# harp_RBG_array_v1_0.net
KiCad netlist of a schematic drawn in EAGLE
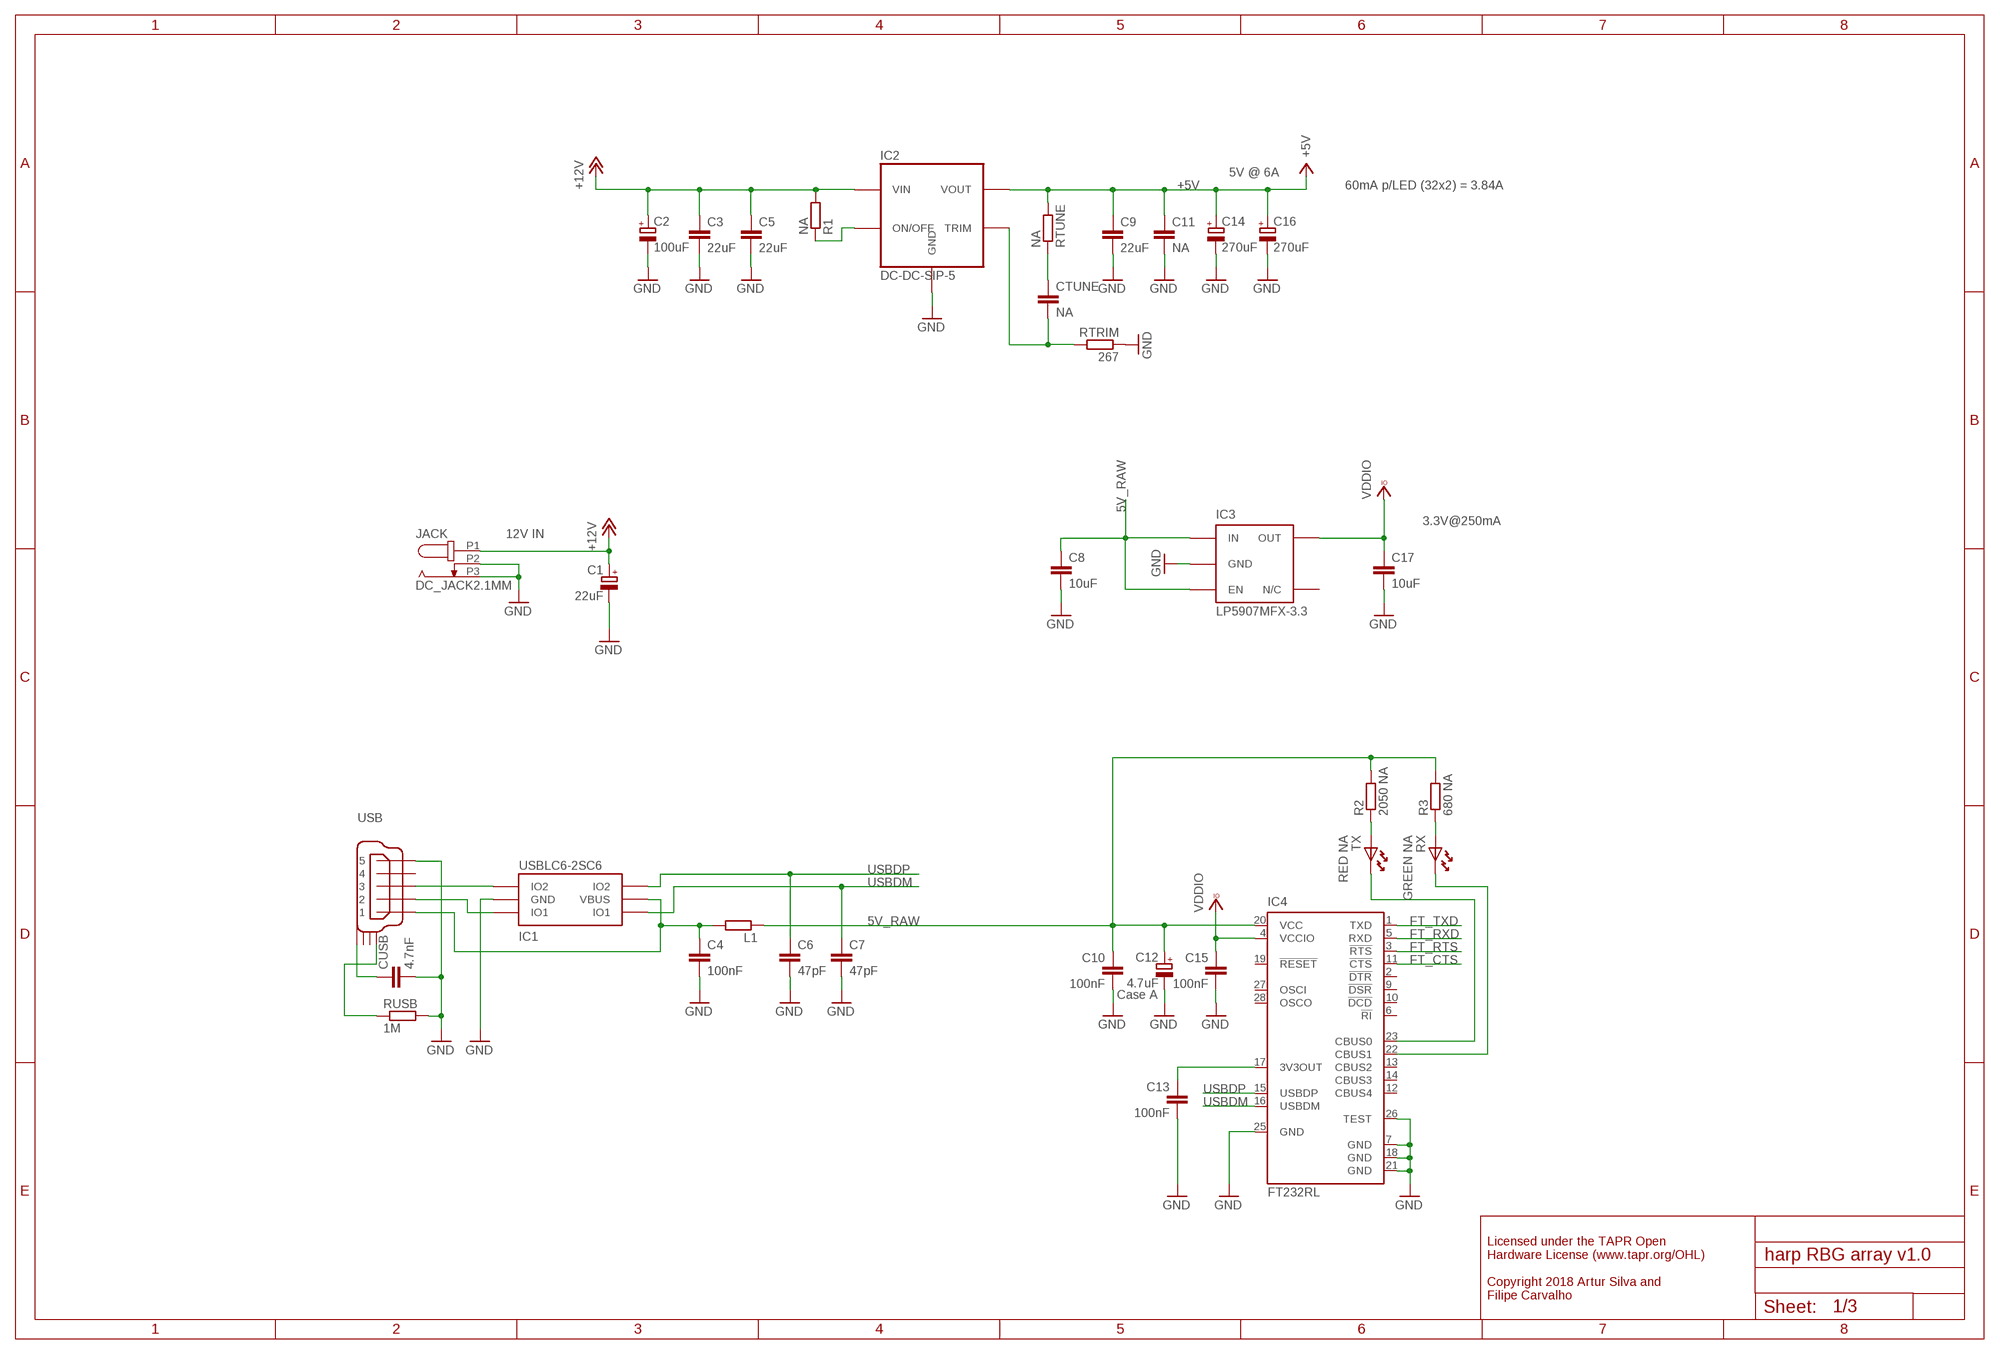
[diagram p0: schematic, sheet 1]
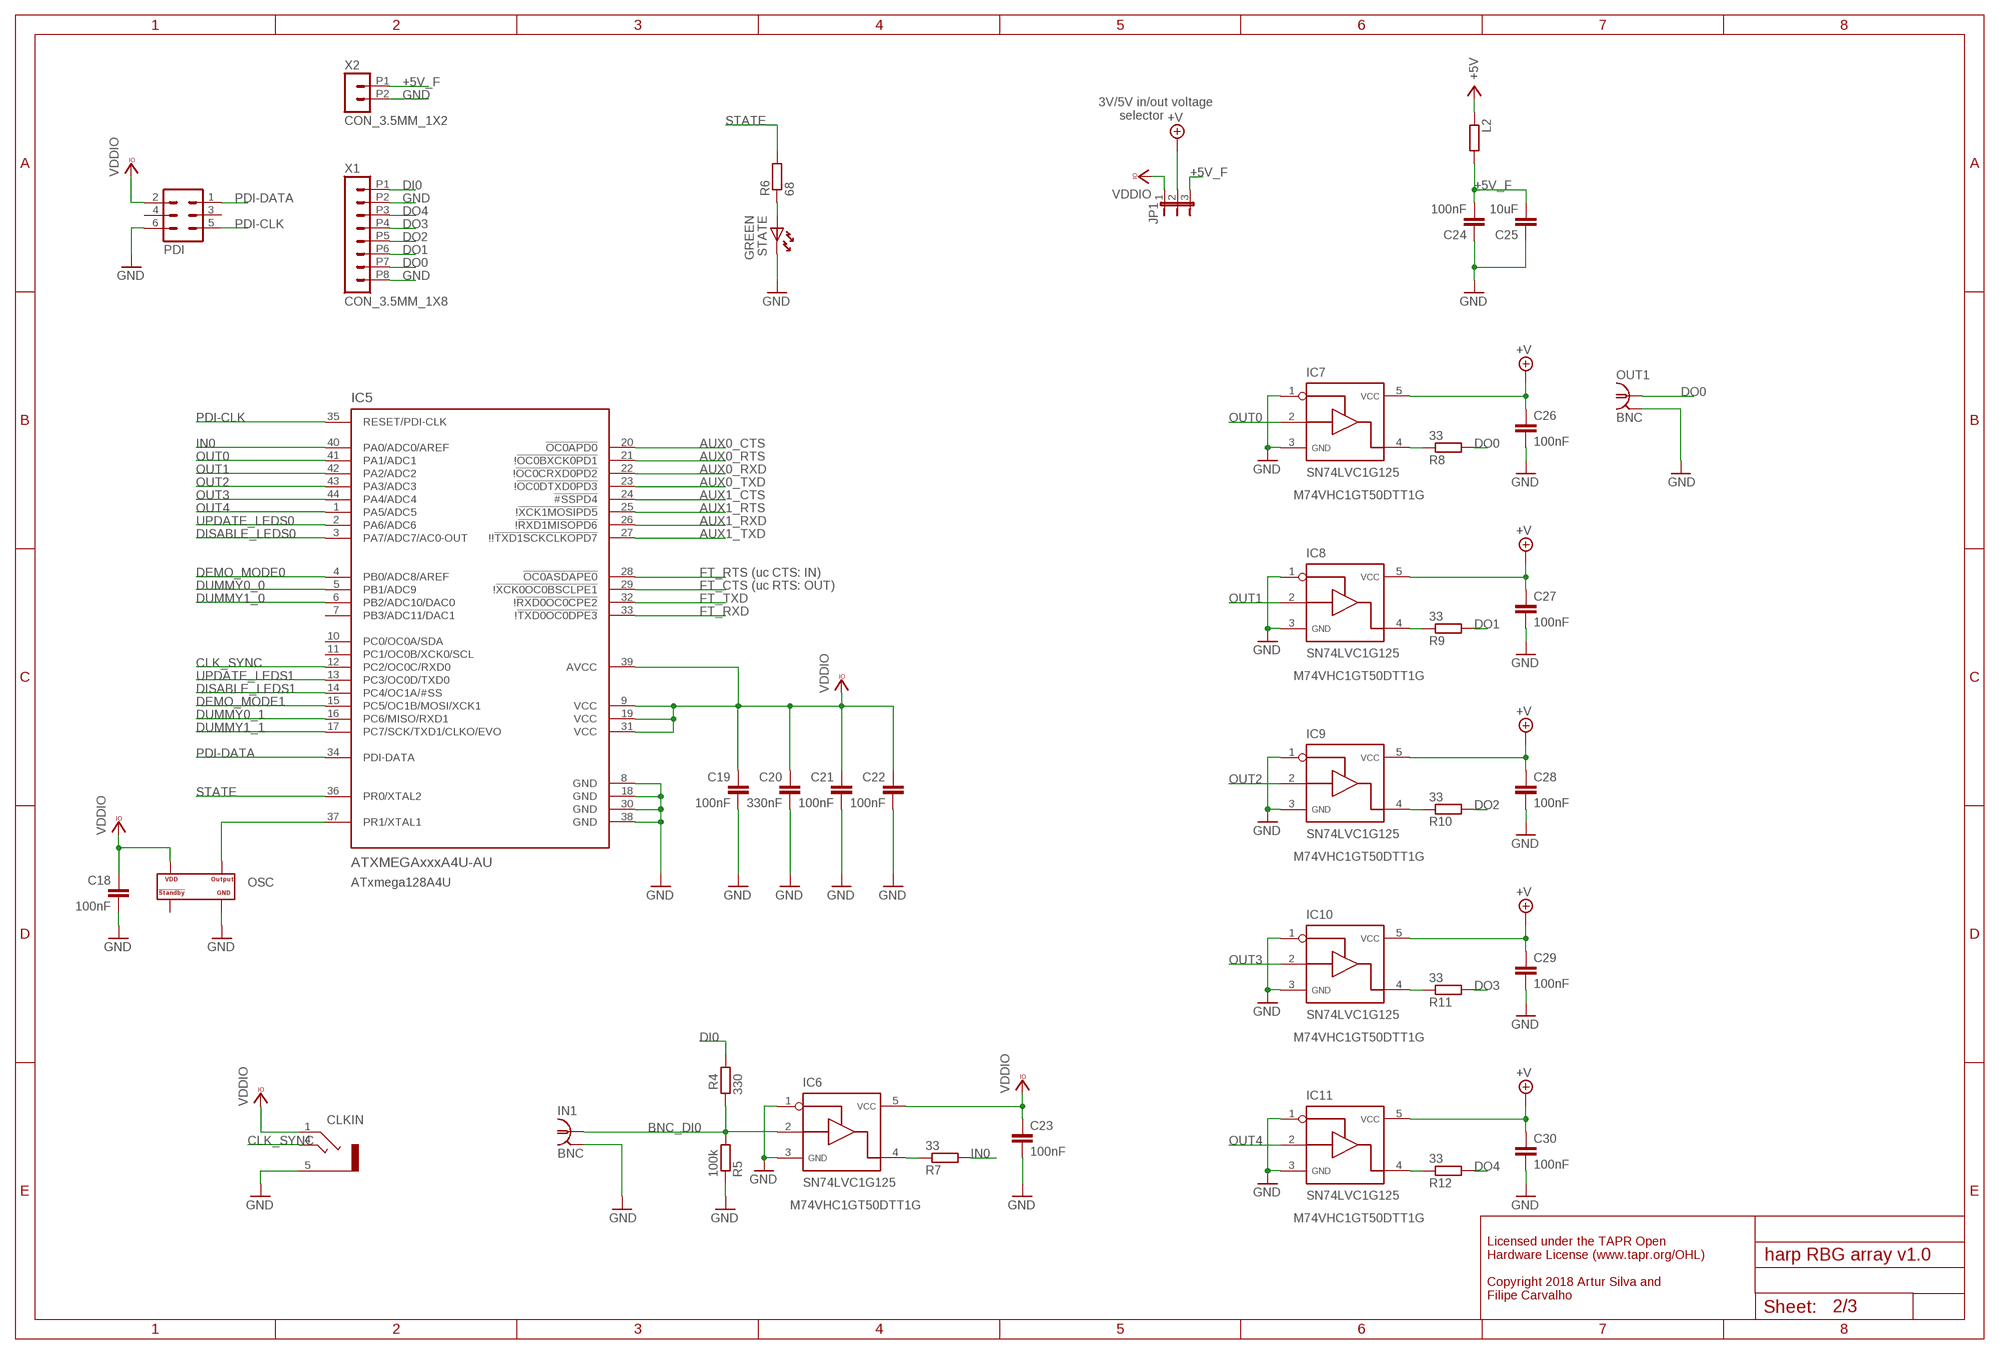
[diagram p1: schematic, sheet 2]
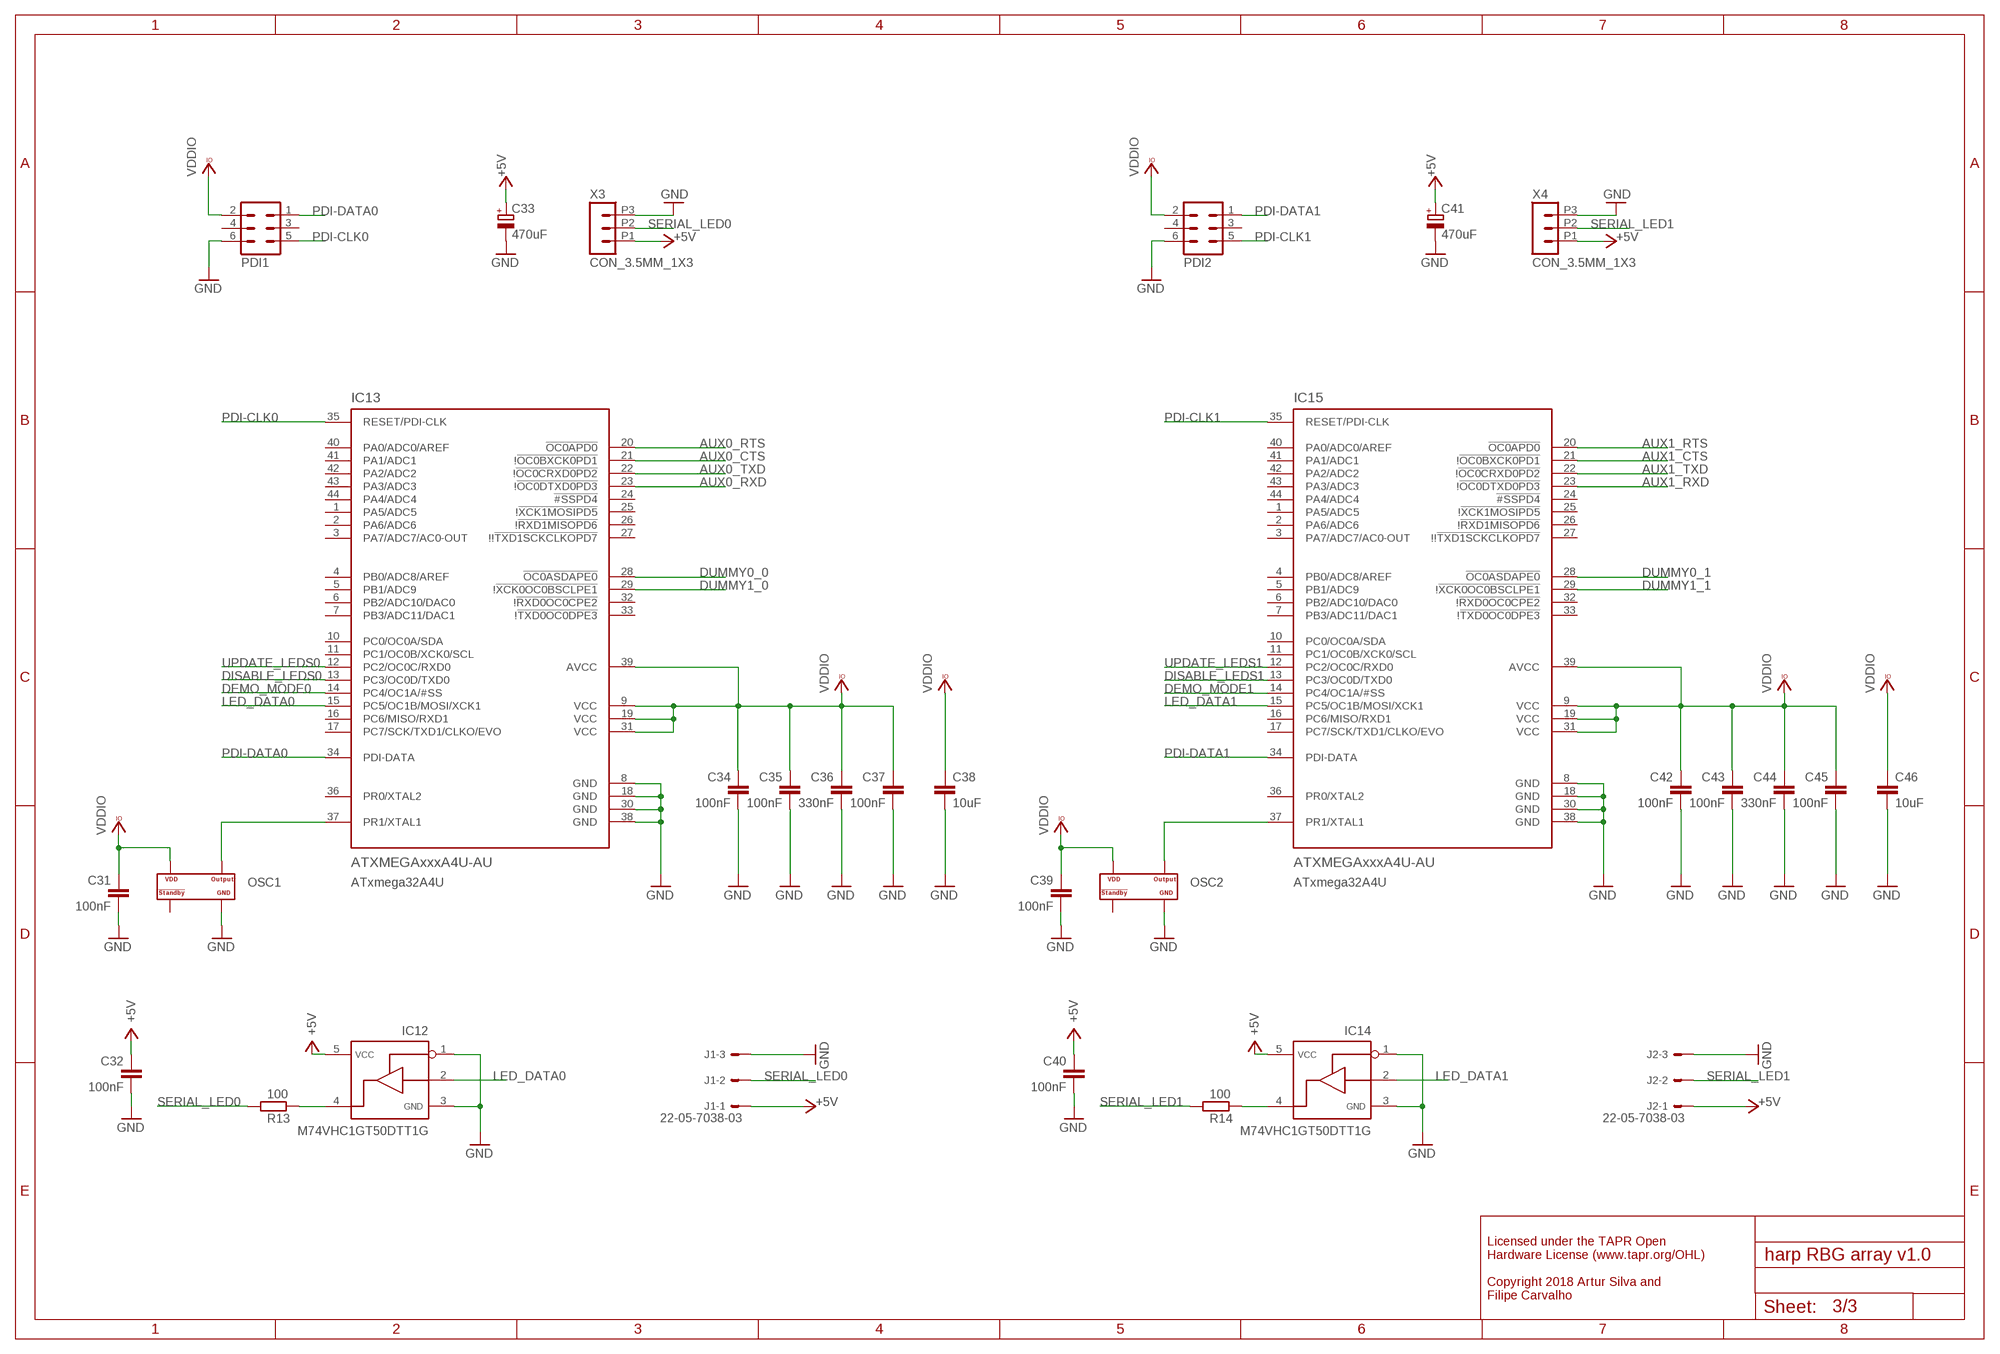
[diagram p2: schematic, sheet 3]

(export (version "E")
  (design (tool "Eeschema 10.0.6"))
  (components
    (comp (ref "C1")
      (value "22uF")
      (footprint "eagle-import:CAP_100UF_HAND")
      (libsource (lib "eagle-import") (part "CAP_100UFHAND"))
    )
    (comp (ref "C2")
      (value "100uF")
      (footprint "eagle-import:PANASONIC_E")
      (libsource (lib "eagle-import") (part "CPOL-EUE"))
    )
    (comp (ref "C3")
      (value "22uF")
      (footprint "eagle-import:C1210")
      (libsource (lib "eagle-import") (part "C-EUC1210"))
    )
    (comp (ref "C4")
      (value "100nF")
      (footprint "eagle-import:C0402")
      (libsource (lib "eagle-import") (part "C-EUC0402"))
    )
    (comp (ref "C5")
      (value "22uF")
      (footprint "eagle-import:C1210")
      (libsource (lib "eagle-import") (part "C-EUC1210"))
    )
    (comp (ref "C6")
      (value "47pF")
      (footprint "eagle-import:C0402")
      (libsource (lib "eagle-import") (part "C-EUC0402"))
    )
    (comp (ref "C7")
      (value "47pF")
      (footprint "eagle-import:C0402")
      (libsource (lib "eagle-import") (part "C-EUC0402"))
    )
    (comp (ref "C8")
      (value "10uF")
      (footprint "eagle-import:C0603")
      (libsource (lib "eagle-import") (part "C-EUC0603"))
    )
    (comp (ref "C9")
      (value "22uF")
      (footprint "eagle-import:C1210")
      (libsource (lib "eagle-import") (part "C-EUC1210"))
    )
    (comp (ref "C10")
      (value "100nF")
      (footprint "eagle-import:C0402")
      (libsource (lib "eagle-import") (part "C-EUC0402"))
    )
    (comp (ref "C11")
      (value "NA")
      (footprint "eagle-import:C1210")
      (libsource (lib "eagle-import") (part "C-EUC1210"))
    )
    (comp (ref "C12")
      (value "4.7uF")
      (footprint "eagle-import:A_3216-18W")
      (libsource (lib "eagle-import") (part "CPOL-EUA/3216-18W"))
    )
    (comp (ref "C13")
      (value "100nF")
      (footprint "eagle-import:C0402")
      (libsource (lib "eagle-import") (part "C-EUC0402"))
    )
    (comp (ref "C14")
      (value "270uF")
      (footprint "eagle-import:PANASONIC_E")
      (libsource (lib "eagle-import") (part "CPOL-EUE"))
    )
    (comp (ref "C15")
      (value "100nF")
      (footprint "eagle-import:C0402")
      (libsource (lib "eagle-import") (part "C-EUC0402"))
    )
    (comp (ref "C16")
      (value "270uF")
      (footprint "eagle-import:PANASONIC_E")
      (libsource (lib "eagle-import") (part "CPOL-EUE"))
    )
    (comp (ref "C17")
      (value "10uF")
      (footprint "eagle-import:C0603")
      (libsource (lib "eagle-import") (part "C-EUC0603"))
    )
    (comp (ref "CTUNE")
      (value "NA")
      (footprint "eagle-import:C0402")
      (libsource (lib "eagle-import") (part "C-EUC0402"))
    )
    (comp (ref "CUSB")
      (value "4.7nF")
      (footprint "eagle-import:C0402")
      (libsource (lib "eagle-import") (part "C-EUC0402"))
    )
    (comp (ref "IC1")
      (value "USBLC6-2SC6")
      (footprint "eagle-import:SOT23-6L")
      (libsource (lib "eagle-import") (part "USBLC6-2"))
    )
    (comp (ref "IC2")
      (value "DC-DC-SIP-5")
      (footprint "eagle-import:SIP-5")
      (libsource (lib "eagle-import") (part "DC-DC-SIP-5"))
    )
    (comp (ref "IC3")
      (value "LP5907MFX-3.3")
      (footprint "eagle-import:TSOT23-5")
      (libsource (lib "eagle-import") (part "TLV700XX"))
    )
    (comp (ref "IC4")
      (value "FT232RL")
      (footprint "eagle-import:SSOP28")
      (libsource (lib "eagle-import") (part "FT232RL"))
    )
    (comp (ref "JACK")
      (value "DC_JACK2.1MM")
      (footprint "eagle-import:DC_POWER_INPUT_2.1MM")
      (libsource (lib "eagle-import") (part "DC_JACK2.1MM"))
    )
    (comp (ref "L1")
      (value "???")
      (footprint "eagle-import:R0805")
      (libsource (lib "eagle-import") (part "R-EU_R0805"))
    )
    (comp (ref "R1")
      (value "NA")
      (footprint "eagle-import:R0402")
      (libsource (lib "eagle-import") (part "R-EU_R0402"))
    )
    (comp (ref "R2")
      (value "2050 NA")
      (footprint "eagle-import:R0402")
      (libsource (lib "eagle-import") (part "R-EU_R0402"))
    )
    (comp (ref "R3")
      (value "680 NA")
      (footprint "eagle-import:R0402")
      (libsource (lib "eagle-import") (part "R-EU_R0402"))
    )
    (comp (ref "RTRIM")
      (value "267")
      (footprint "eagle-import:R0402")
      (libsource (lib "eagle-import") (part "R-EU_R0402"))
    )
    (comp (ref "RTUNE")
      (value "NA")
      (footprint "eagle-import:R0402")
      (libsource (lib "eagle-import") (part "R-EU_R0402"))
    )
    (comp (ref "RUSB")
      (value "1M")
      (footprint "eagle-import:R0402")
      (libsource (lib "eagle-import") (part "R-EU_R0402"))
    )
    (comp (ref "RX")
      (value "GREEN NA")
      (footprint "eagle-import:LED_HAND")
      (libsource (lib "eagle-import") (part "LEDHAND"))
    )
    (comp (ref "TX")
      (value "RED NA")
      (footprint "eagle-import:LED_HAND")
      (libsource (lib "eagle-import") (part "LEDHAND"))
    )
    (comp (ref "USB")
      (value "USB_MINI_B")
      (footprint "eagle-import:240-0002-1")
      (libsource (lib "eagle-import") (part "USB_MINI_B"))
    )
    (comp (ref "C31")
      (value "100nF")
      (footprint "eagle-import:C0402")
      (libsource (lib "eagle-import") (part "C-EUC0402"))
    )
    (comp (ref "C32")
      (value "100nF")
      (footprint "eagle-import:C0402")
      (libsource (lib "eagle-import") (part "C-EUC0402"))
    )
    (comp (ref "C33")
      (value "470uF")
      (footprint "eagle-import:E3,5-8")
      (libsource (lib "eagle-import") (part "resistor_CPOL-EUE3.5-8"))
    )
    (comp (ref "C34")
      (value "100nF")
      (footprint "eagle-import:C0402")
      (libsource (lib "eagle-import") (part "C-EUC0402"))
    )
    (comp (ref "C35")
      (value "100nF")
      (footprint "eagle-import:C0402")
      (libsource (lib "eagle-import") (part "C-EUC0402"))
    )
    (comp (ref "C36")
      (value "330nF")
      (footprint "eagle-import:C0402")
      (libsource (lib "eagle-import") (part "C-EUC0402"))
    )
    (comp (ref "C37")
      (value "100nF")
      (footprint "eagle-import:C0402")
      (libsource (lib "eagle-import") (part "C-EUC0402"))
    )
    (comp (ref "C38")
      (value "10uF")
      (footprint "eagle-import:C0603")
      (libsource (lib "eagle-import") (part "C-EUC0603"))
    )
    (comp (ref "C39")
      (value "100nF")
      (footprint "eagle-import:C0402")
      (libsource (lib "eagle-import") (part "C-EUC0402"))
    )
    (comp (ref "C40")
      (value "100nF")
      (footprint "eagle-import:C0402")
      (libsource (lib "eagle-import") (part "C-EUC0402"))
    )
    (comp (ref "C41")
      (value "470uF")
      (footprint "eagle-import:E3,5-8")
      (libsource (lib "eagle-import") (part "resistor_CPOL-EUE3.5-8"))
    )
    (comp (ref "C42")
      (value "100nF")
      (footprint "eagle-import:C0402")
      (libsource (lib "eagle-import") (part "C-EUC0402"))
    )
    (comp (ref "C43")
      (value "100nF")
      (footprint "eagle-import:C0402")
      (libsource (lib "eagle-import") (part "C-EUC0402"))
    )
    (comp (ref "C44")
      (value "330nF")
      (footprint "eagle-import:C0402")
      (libsource (lib "eagle-import") (part "C-EUC0402"))
    )
    (comp (ref "C45")
      (value "100nF")
      (footprint "eagle-import:C0402")
      (libsource (lib "eagle-import") (part "C-EUC0402"))
    )
    (comp (ref "C46")
      (value "10uF")
      (footprint "eagle-import:C0603")
      (libsource (lib "eagle-import") (part "C-EUC0603"))
    )
    (comp (ref "IC12")
      (value "M74VHC1GT50DTT1G")
      (footprint "eagle-import:SOT23-5")
      (libsource (lib "eagle-import") (part "SN74LVC1G125"))
    )
    (comp (ref "IC13")
      (value "ATXMEGAxxxA4U-AU")
      (footprint "eagle-import:QFP80P1200X1200X120-44N")
      (libsource (lib "eagle-import") (part "AT-XMEGA-XXA4-AU"))
    )
    (comp (ref "IC14")
      (value "M74VHC1GT50DTT1G")
      (footprint "eagle-import:SOT23-5")
      (libsource (lib "eagle-import") (part "SN74LVC1G125"))
    )
    (comp (ref "IC15")
      (value "ATXMEGAxxxA4U-AU")
      (footprint "eagle-import:QFP80P1200X1200X120-44N")
      (libsource (lib "eagle-import") (part "AT-XMEGA-XXA4-AU"))
    )
    (comp (ref "J1")
      (value "22-05-7038-03")
      (footprint "eagle-import:7395-03")
      (libsource (lib "eagle-import") (part "22-?-0305-7038"))
    )
    (comp (ref "J2")
      (value "22-05-7038-03")
      (footprint "eagle-import:7395-03")
      (libsource (lib "eagle-import") (part "22-?-0305-7038"))
    )
    (comp (ref "OSC1")
      (value "OSCILLATOR")
      (footprint "eagle-import:OSCILLATOR_3.2X2.5")
      (libsource (lib "eagle-import") (part "OSCILLATOR"))
    )
    (comp (ref "OSC2")
      (value "OSCILLATOR")
      (footprint "eagle-import:OSCILLATOR_3.2X2.5")
      (libsource (lib "eagle-import") (part "OSCILLATOR"))
    )
    (comp (ref "PDI1")
      (value "MA03-2")
      (footprint "eagle-import:MA03-2")
      (libsource (lib "eagle-import") (part "MA03-2"))
    )
    (comp (ref "PDI2")
      (value "MA03-2")
      (footprint "eagle-import:MA03-2")
      (libsource (lib "eagle-import") (part "MA03-2"))
    )
    (comp (ref "R13")
      (value "100")
      (footprint "eagle-import:R0402")
      (libsource (lib "eagle-import") (part "R-EU_R0402"))
    )
    (comp (ref "R14")
      (value "100")
      (footprint "eagle-import:R0402")
      (libsource (lib "eagle-import") (part "R-EU_R0402"))
    )
    (comp (ref "X3")
      (value "CON_3.5MM_1X3")
      (footprint "eagle-import:CON_3.5MM_1X3")
      (libsource (lib "eagle-import") (part "CON_3.5MM_1X3"))
    )
    (comp (ref "X4")
      (value "CON_3.5MM_1X3")
      (footprint "eagle-import:CON_3.5MM_1X3")
      (libsource (lib "eagle-import") (part "CON_3.5MM_1X3"))
    )
    (comp (ref "C18")
      (value "100nF")
      (footprint "eagle-import:C0402")
      (libsource (lib "eagle-import") (part "C-EUC0402"))
    )
    (comp (ref "C19")
      (value "100nF")
      (footprint "eagle-import:C0402")
      (libsource (lib "eagle-import") (part "C-EUC0402"))
    )
    (comp (ref "C20")
      (value "330nF")
      (footprint "eagle-import:C0402")
      (libsource (lib "eagle-import") (part "C-EUC0402"))
    )
    (comp (ref "C21")
      (value "100nF")
      (footprint "eagle-import:C0402")
      (libsource (lib "eagle-import") (part "C-EUC0402"))
    )
    (comp (ref "C22")
      (value "100nF")
      (footprint "eagle-import:C0402")
      (libsource (lib "eagle-import") (part "C-EUC0402"))
    )
    (comp (ref "C23")
      (value "100nF")
      (footprint "eagle-import:C0402")
      (libsource (lib "eagle-import") (part "C-EUC0402"))
    )
    (comp (ref "C24")
      (value "100nF")
      (footprint "eagle-import:C0402")
      (libsource (lib "eagle-import") (part "C-EUC0402"))
    )
    (comp (ref "C25")
      (value "10uF")
      (footprint "eagle-import:C0603")
      (libsource (lib "eagle-import") (part "C-EUC0603"))
    )
    (comp (ref "C26")
      (value "100nF")
      (footprint "eagle-import:C0402")
      (libsource (lib "eagle-import") (part "C-EUC0402"))
    )
    (comp (ref "C27")
      (value "100nF")
      (footprint "eagle-import:C0402")
      (libsource (lib "eagle-import") (part "C-EUC0402"))
    )
    (comp (ref "C28")
      (value "100nF")
      (footprint "eagle-import:C0402")
      (libsource (lib "eagle-import") (part "C-EUC0402"))
    )
    (comp (ref "C29")
      (value "100nF")
      (footprint "eagle-import:C0402")
      (libsource (lib "eagle-import") (part "C-EUC0402"))
    )
    (comp (ref "C30")
      (value "100nF")
      (footprint "eagle-import:C0402")
      (libsource (lib "eagle-import") (part "C-EUC0402"))
    )
    (comp (ref "CLKIN")
      (value "STEREO_JACK")
      (footprint "eagle-import:35RASMT2BHNTRX")
      (libsource (lib "eagle-import") (part "STEREO_JACK"))
    )
    (comp (ref "IC5")
      (value "ATXMEGAxxxA4U-AU")
      (footprint "eagle-import:QFP80P1200X1200X120-44N")
      (libsource (lib "eagle-import") (part "AT-XMEGA-XXA4-AU"))
    )
    (comp (ref "IC6")
      (value "SN74LVC1G125")
      (footprint "eagle-import:SOT23-5")
      (libsource (lib "eagle-import") (part "SN74LVC1G125"))
    )
    (comp (ref "IC7")
      (value "SN74LVC1G125")
      (footprint "eagle-import:SOT23-5")
      (libsource (lib "eagle-import") (part "SN74LVC1G125"))
    )
    (comp (ref "IC8")
      (value "SN74LVC1G125")
      (footprint "eagle-import:SOT23-5")
      (libsource (lib "eagle-import") (part "SN74LVC1G125"))
    )
    (comp (ref "IC9")
      (value "SN74LVC1G125")
      (footprint "eagle-import:SOT23-5")
      (libsource (lib "eagle-import") (part "SN74LVC1G125"))
    )
    (comp (ref "IC10")
      (value "SN74LVC1G125")
      (footprint "eagle-import:SOT23-5")
      (libsource (lib "eagle-import") (part "SN74LVC1G125"))
    )
    (comp (ref "IC11")
      (value "SN74LVC1G125")
      (footprint "eagle-import:SOT23-5")
      (libsource (lib "eagle-import") (part "SN74LVC1G125"))
    )
    (comp (ref "IN1")
      (value "BNC")
      (footprint "eagle-import:BNC_RA")
      (libsource (lib "eagle-import") (part "BNC"))
    )
    (comp (ref "JP1")
      (value "JP2E")
      (footprint "eagle-import:JP2")
      (libsource (lib "eagle-import") (part "JP2E"))
    )
    (comp (ref "L2")
      (value "600@100M")
      (footprint "eagle-import:R0805")
      (libsource (lib "eagle-import") (part "R-EU_R0805"))
    )
    (comp (ref "OSC")
      (value "OSCILLATOR")
      (footprint "eagle-import:OSCILLATOR_3.2X2.5")
      (libsource (lib "eagle-import") (part "OSCILLATOR"))
    )
    (comp (ref "OUT1")
      (value "BNC")
      (footprint "eagle-import:BNC_RA")
      (libsource (lib "eagle-import") (part "BNC"))
    )
    (comp (ref "PDI")
      (value "MA03-2")
      (footprint "eagle-import:MA03-2")
      (libsource (lib "eagle-import") (part "MA03-2"))
    )
    (comp (ref "R4")
      (value "330")
      (footprint "eagle-import:R0402")
      (libsource (lib "eagle-import") (part "R-EU_R0402"))
    )
    (comp (ref "R5")
      (value "100k")
      (footprint "eagle-import:R0402")
      (libsource (lib "eagle-import") (part "R-EU_R0402"))
    )
    (comp (ref "R6")
      (value "68")
      (footprint "eagle-import:R0402")
      (libsource (lib "eagle-import") (part "R-EU_R0402"))
    )
    (comp (ref "R7")
      (value "33")
      (footprint "eagle-import:R0402")
      (libsource (lib "eagle-import") (part "R-EU_R0402"))
    )
    (comp (ref "R8")
      (value "33")
      (footprint "eagle-import:R0402")
      (libsource (lib "eagle-import") (part "R-EU_R0402"))
    )
    (comp (ref "R9")
      (value "33")
      (footprint "eagle-import:R0402")
      (libsource (lib "eagle-import") (part "R-EU_R0402"))
    )
    (comp (ref "R10")
      (value "33")
      (footprint "eagle-import:R0402")
      (libsource (lib "eagle-import") (part "R-EU_R0402"))
    )
    (comp (ref "R11")
      (value "33")
      (footprint "eagle-import:R0402")
      (libsource (lib "eagle-import") (part "R-EU_R0402"))
    )
    (comp (ref "R12")
      (value "33")
      (footprint "eagle-import:R0402")
      (libsource (lib "eagle-import") (part "R-EU_R0402"))
    )
    (comp (ref "STATE")
      (value "GREEN")
      (footprint "eagle-import:LED_HAND")
      (libsource (lib "eagle-import") (part "LEDHAND"))
    )
    (comp (ref "X1")
      (value "CON_3.5MM_1X8")
      (footprint "eagle-import:CON_3.5MM_1X8")
      (libsource (lib "eagle-import") (part "CON_3.5MM_1X8"))
    )
    (comp (ref "X2")
      (value "CON_3.5MM_1X2")
      (footprint "eagle-import:CON_3.5MM_1X2")
      (libsource (lib "eagle-import") (part "CON_3.5MM_1X2"))
    )
  )
  (nets
    (net (code "1") (name "+5V") (class "Default")
      (node (ref "C11") (pin "1") (pinfunction "1_1") (pintype "passive"))
      (node (ref "C14") (pin "+") (pinfunction "+_+") (pintype "passive"))
      (node (ref "C16") (pin "+") (pinfunction "+_+") (pintype "passive"))
      (node (ref "C32") (pin "1") (pinfunction "1_1") (pintype "passive"))
      (node (ref "C33") (pin "+") (pinfunction "+_+") (pintype "passive"))
      (node (ref "C40") (pin "1") (pinfunction "1_1") (pintype "passive"))
      (node (ref "C41") (pin "+") (pinfunction "+_+") (pintype "passive"))
      (node (ref "C9") (pin "1") (pinfunction "1_1") (pintype "passive"))
      (node (ref "IC12") (pin "5") (pinfunction "P$5_5") (pintype "bidirectional"))
      (node (ref "IC14") (pin "5") (pinfunction "P$5_5") (pintype "bidirectional"))
      (node (ref "IC2") (pin "P4") (pinfunction "VOUT_P4") (pintype "passive"))
      (node (ref "J1") (pin "1") (pinfunction "S_1") (pintype "passive"))
      (node (ref "J2") (pin "1") (pinfunction "S_1") (pintype "passive"))
      (node (ref "L2") (pin "1") (pinfunction "1_1") (pintype "passive"))
      (node (ref "RTUNE") (pin "2") (pinfunction "2_2") (pintype "passive"))
      (node (ref "X3") (pin "P1") (pinfunction "1_P1") (pintype "passive"))
      (node (ref "X4") (pin "P1") (pinfunction "1_P1") (pintype "passive"))
    )
    (net (code "2") (name "+5V_F") (class "Default")
      (node (ref "C24") (pin "2") (pinfunction "2_2") (pintype "passive"))
      (node (ref "C25") (pin "2") (pinfunction "2_2") (pintype "passive"))
      (node (ref "JP1") (pin "3") (pinfunction "3_3") (pintype "passive"))
      (node (ref "L2") (pin "2") (pinfunction "2_2") (pintype "passive"))
      (node (ref "X2") (pin "P1") (pinfunction "1_P1") (pintype "passive"))
    )
    (net (code "3") (name "+12V") (class "Default")
      (node (ref "C1") (pin "+") (pinfunction "+_+") (pintype "passive"))
      (node (ref "C2") (pin "+") (pinfunction "+_+") (pintype "passive"))
      (node (ref "C3") (pin "1") (pinfunction "1_1") (pintype "passive"))
      (node (ref "C5") (pin "1") (pinfunction "1_1") (pintype "passive"))
      (node (ref "IC2") (pin "P2") (pinfunction "VIN_P2") (pintype "passive"))
      (node (ref "JACK") (pin "P1") (pinfunction "1_P1") (pintype "passive"))
      (node (ref "R1") (pin "2") (pinfunction "2_2") (pintype "passive"))
    )
    (net (code "4") (name "+V") (class "Default")
      (node (ref "C26") (pin "1") (pinfunction "1_1") (pintype "passive"))
      (node (ref "C27") (pin "1") (pinfunction "1_1") (pintype "passive"))
      (node (ref "C28") (pin "1") (pinfunction "1_1") (pintype "passive"))
      (node (ref "C29") (pin "1") (pinfunction "1_1") (pintype "passive"))
      (node (ref "C30") (pin "1") (pinfunction "1_1") (pintype "passive"))
      (node (ref "IC10") (pin "5") (pinfunction "P$5_5") (pintype "bidirectional"))
      (node (ref "IC11") (pin "5") (pinfunction "P$5_5") (pintype "bidirectional"))
      (node (ref "IC7") (pin "5") (pinfunction "P$5_5") (pintype "bidirectional"))
      (node (ref "IC8") (pin "5") (pinfunction "P$5_5") (pintype "bidirectional"))
      (node (ref "IC9") (pin "5") (pinfunction "P$5_5") (pintype "bidirectional"))
      (node (ref "JP1") (pin "2") (pinfunction "2_2") (pintype "passive"))
    )
    (net (code "5") (name "5V_RAW") (class "Default")
      (node (ref "C10") (pin "1") (pinfunction "1_1") (pintype "passive"))
      (node (ref "C12") (pin "+") (pinfunction "+_+") (pintype "passive"))
      (node (ref "C8") (pin "1") (pinfunction "1_1") (pintype "passive"))
      (node (ref "IC3") (pin "1") (pinfunction "IN_1") (pintype "bidirectional"))
      (node (ref "IC3") (pin "3") (pinfunction "EN_3") (pintype "bidirectional"))
      (node (ref "IC4") (pin "20") (pinfunction "VCC_20") (pintype "power_in"))
      (node (ref "L1") (pin "1") (pinfunction "1_1") (pintype "passive"))
      (node (ref "R2") (pin "2") (pinfunction "2_2") (pintype "passive"))
      (node (ref "R3") (pin "2") (pinfunction "2_2") (pintype "passive"))
    )
    (net (code "6") (name "AUX0_CTS") (class "Default")
      (node (ref "IC13") (pin "21") (pinfunction "~OC0BXCK0PD1_21") (pintype "bidirectional"))
      (node (ref "IC5") (pin "20") (pinfunction "~{OC0APD0}_20") (pintype "bidirectional"))
    )
    (net (code "7") (name "AUX0_RTS") (class "Default")
      (node (ref "IC13") (pin "20") (pinfunction "~{OC0APD0}_20") (pintype "bidirectional"))
      (node (ref "IC5") (pin "21") (pinfunction "~OC0BXCK0PD1_21") (pintype "bidirectional"))
    )
    (net (code "8") (name "AUX0_RXD") (class "Default")
      (node (ref "IC13") (pin "23") (pinfunction "~OC0DTXD0PD3_23") (pintype "bidirectional"))
      (node (ref "IC5") (pin "22") (pinfunction "~OC0CRXD0PD2_22") (pintype "bidirectional"))
    )
    (net (code "9") (name "AUX0_TXD") (class "Default")
      (node (ref "IC13") (pin "22") (pinfunction "~OC0CRXD0PD2_22") (pintype "bidirectional"))
      (node (ref "IC5") (pin "23") (pinfunction "~OC0DTXD0PD3_23") (pintype "bidirectional"))
    )
    (net (code "10") (name "AUX1_CTS") (class "Default")
      (node (ref "IC15") (pin "21") (pinfunction "~OC0BXCK0PD1_21") (pintype "bidirectional"))
      (node (ref "IC5") (pin "24") (pinfunction "~{#SSPD4}_24") (pintype "bidirectional"))
    )
    (net (code "11") (name "AUX1_RTS") (class "Default")
      (node (ref "IC15") (pin "20") (pinfunction "~{OC0APD0}_20") (pintype "bidirectional"))
      (node (ref "IC5") (pin "25") (pinfunction "~XCK1MOSIPD5_25") (pintype "bidirectional"))
    )
    (net (code "12") (name "AUX1_RXD") (class "Default")
      (node (ref "IC15") (pin "23") (pinfunction "~OC0DTXD0PD3_23") (pintype "bidirectional"))
      (node (ref "IC5") (pin "26") (pinfunction "~RXD1MISOPD6_26") (pintype "bidirectional"))
    )
    (net (code "13") (name "AUX1_TXD") (class "Default")
      (node (ref "IC15") (pin "22") (pinfunction "~OC0CRXD0PD2_22") (pintype "bidirectional"))
      (node (ref "IC5") (pin "27") (pinfunction "~~{TXD1SCKCLKOPD7}_27") (pintype "bidirectional"))
    )
    (net (code "14") (name "BNC_DI0") (class "Default")
      (node (ref "IC6") (pin "2") (pinfunction "P$2_2") (pintype "bidirectional"))
      (node (ref "IN1") (pin "1") (pinfunction "1_1") (pintype "passive"))
      (node (ref "R4") (pin "2") (pinfunction "2_2") (pintype "passive"))
      (node (ref "R5") (pin "2") (pinfunction "2_2") (pintype "passive"))
    )
    (net (code "15") (name "CLK_SYNC") (class "Default")
      (node (ref "CLKIN") (pin "4") (pinfunction "4_4") (pintype "passive"))
      (node (ref "IC5") (pin "12") (pinfunction "PC2/OC0C/RXD0_12") (pintype "bidirectional"))
    )
    (net (code "16") (name "DEMO_MODE0") (class "Default")
      (node (ref "IC13") (pin "14") (pinfunction "PC4/OC1A/#SS_14") (pintype "bidirectional"))
      (node (ref "IC5") (pin "4") (pinfunction "PB0/ADC8/AREF_4") (pintype "bidirectional"))
    )
    (net (code "17") (name "DEMO_MODE1") (class "Default")
      (node (ref "IC15") (pin "14") (pinfunction "PC4/OC1A/#SS_14") (pintype "bidirectional"))
      (node (ref "IC5") (pin "15") (pinfunction "PC5/OC1B/MOSI/XCK1_15") (pintype "bidirectional"))
    )
    (net (code "18") (name "DI0") (class "Default")
      (node (ref "R4") (pin "1") (pinfunction "1_1") (pintype "passive"))
      (node (ref "X1") (pin "P1") (pinfunction "1_P1") (pintype "passive"))
    )
    (net (code "19") (name "DISABLE_LEDS0") (class "Default")
      (node (ref "IC13") (pin "13") (pinfunction "PC3/OC0D/TXD0_13") (pintype "bidirectional"))
      (node (ref "IC5") (pin "3") (pinfunction "PA7/ADC7/AC0-OUT_3") (pintype "bidirectional"))
    )
    (net (code "20") (name "DISABLE_LEDS1") (class "Default")
      (node (ref "IC15") (pin "13") (pinfunction "PC3/OC0D/TXD0_13") (pintype "bidirectional"))
      (node (ref "IC5") (pin "14") (pinfunction "PC4/OC1A/#SS_14") (pintype "bidirectional"))
    )
    (net (code "21") (name "DO0") (class "Default")
      (node (ref "OUT1") (pin "1") (pinfunction "1_1") (pintype "passive"))
      (node (ref "R8") (pin "2") (pinfunction "2_2") (pintype "passive"))
      (node (ref "X1") (pin "P7") (pinfunction "7_P7") (pintype "passive"))
    )
    (net (code "22") (name "DO1") (class "Default")
      (node (ref "R9") (pin "2") (pinfunction "2_2") (pintype "passive"))
      (node (ref "X1") (pin "P6") (pinfunction "6_P6") (pintype "passive"))
    )
    (net (code "23") (name "DO2") (class "Default")
      (node (ref "R10") (pin "2") (pinfunction "2_2") (pintype "passive"))
      (node (ref "X1") (pin "P5") (pinfunction "5_P5") (pintype "passive"))
    )
    (net (code "24") (name "DO3") (class "Default")
      (node (ref "R11") (pin "2") (pinfunction "2_2") (pintype "passive"))
      (node (ref "X1") (pin "P4") (pinfunction "4_P4") (pintype "passive"))
    )
    (net (code "25") (name "DO4") (class "Default")
      (node (ref "R12") (pin "2") (pinfunction "2_2") (pintype "passive"))
      (node (ref "X1") (pin "P3") (pinfunction "3_P3") (pintype "passive"))
    )
    (net (code "26") (name "DUMMY0_0") (class "Default")
      (node (ref "IC13") (pin "28") (pinfunction "~{OC0ASDAPE0}_28") (pintype "bidirectional"))
      (node (ref "IC5") (pin "5") (pinfunction "PB1/ADC9_5") (pintype "bidirectional"))
    )
    (net (code "27") (name "DUMMY0_1") (class "Default")
      (node (ref "IC15") (pin "28") (pinfunction "~{OC0ASDAPE0}_28") (pintype "bidirectional"))
      (node (ref "IC5") (pin "16") (pinfunction "PC6/MISO/RXD1_16") (pintype "bidirectional"))
    )
    (net (code "28") (name "DUMMY1_0") (class "Default")
      (node (ref "IC13") (pin "29") (pinfunction "~XCK0OC0BSCLPE1_29") (pintype "bidirectional"))
      (node (ref "IC5") (pin "6") (pinfunction "PB2/ADC10/DAC0_6") (pintype "bidirectional"))
    )
    (net (code "29") (name "DUMMY1_1") (class "Default")
      (node (ref "IC15") (pin "29") (pinfunction "~XCK0OC0BSCLPE1_29") (pintype "bidirectional"))
      (node (ref "IC5") (pin "17") (pinfunction "PC7/SCK/TXD1/CLKO/EVO_17") (pintype "bidirectional"))
    )
    (net (code "30") (name "FT_CTS") (class "Default")
      (node (ref "IC4") (pin "11") (pinfunction "~{CTS}_11") (pintype "input"))
      (node (ref "IC5") (pin "29") (pinfunction "~XCK0OC0BSCLPE1_29") (pintype "bidirectional"))
    )
    (net (code "31") (name "FT_RTS") (class "Default")
      (node (ref "IC4") (pin "3") (pinfunction "~{RTS}_3") (pintype "output"))
      (node (ref "IC5") (pin "28") (pinfunction "~{OC0ASDAPE0}_28") (pintype "bidirectional"))
    )
    (net (code "32") (name "FT_RXD") (class "Default")
      (node (ref "IC4") (pin "5") (pinfunction "RXD_5") (pintype "input"))
      (node (ref "IC5") (pin "33") (pinfunction "~TXD0OC0DPE3_33") (pintype "bidirectional"))
    )
    (net (code "33") (name "FT_TXD") (class "Default")
      (node (ref "IC4") (pin "1") (pinfunction "TXD_1") (pintype "output"))
      (node (ref "IC5") (pin "32") (pinfunction "~RXD0OC0CPE2_32") (pintype "bidirectional"))
    )
    (net (code "34") (name "GND") (class "Default")
      (node (ref "C1") (pin "-") (pinfunction "-_-") (pintype "passive"))
      (node (ref "C10") (pin "2") (pinfunction "2_2") (pintype "passive"))
      (node (ref "C11") (pin "2") (pinfunction "2_2") (pintype "passive"))
      (node (ref "C12") (pin "-") (pinfunction "-_-") (pintype "passive"))
      (node (ref "C13") (pin "2") (pinfunction "2_2") (pintype "passive"))
      (node (ref "C14") (pin "-") (pinfunction "-_-") (pintype "passive"))
      (node (ref "C15") (pin "2") (pinfunction "2_2") (pintype "passive"))
      (node (ref "C16") (pin "-") (pinfunction "-_-") (pintype "passive"))
      (node (ref "C17") (pin "2") (pinfunction "2_2") (pintype "passive"))
      (node (ref "C18") (pin "2") (pinfunction "2_2") (pintype "passive"))
      (node (ref "C19") (pin "2") (pinfunction "2_2") (pintype "passive"))
      (node (ref "C2") (pin "-") (pinfunction "-_-") (pintype "passive"))
      (node (ref "C20") (pin "2") (pinfunction "2_2") (pintype "passive"))
      (node (ref "C21") (pin "2") (pinfunction "2_2") (pintype "passive"))
      (node (ref "C22") (pin "2") (pinfunction "2_2") (pintype "passive"))
      (node (ref "C23") (pin "2") (pinfunction "2_2") (pintype "passive"))
      (node (ref "C24") (pin "1") (pinfunction "1_1") (pintype "passive"))
      (node (ref "C25") (pin "1") (pinfunction "1_1") (pintype "passive"))
      (node (ref "C26") (pin "2") (pinfunction "2_2") (pintype "passive"))
      (node (ref "C27") (pin "2") (pinfunction "2_2") (pintype "passive"))
      (node (ref "C28") (pin "2") (pinfunction "2_2") (pintype "passive"))
      (node (ref "C29") (pin "2") (pinfunction "2_2") (pintype "passive"))
      (node (ref "C3") (pin "2") (pinfunction "2_2") (pintype "passive"))
      (node (ref "C30") (pin "2") (pinfunction "2_2") (pintype "passive"))
      (node (ref "C31") (pin "2") (pinfunction "2_2") (pintype "passive"))
      (node (ref "C32") (pin "2") (pinfunction "2_2") (pintype "passive"))
      (node (ref "C33") (pin "-") (pinfunction "-_-") (pintype "passive"))
      (node (ref "C34") (pin "2") (pinfunction "2_2") (pintype "passive"))
      (node (ref "C35") (pin "2") (pinfunction "2_2") (pintype "passive"))
      (node (ref "C36") (pin "2") (pinfunction "2_2") (pintype "passive"))
      (node (ref "C37") (pin "2") (pinfunction "2_2") (pintype "passive"))
      (node (ref "C38") (pin "2") (pinfunction "2_2") (pintype "passive"))
      (node (ref "C39") (pin "2") (pinfunction "2_2") (pintype "passive"))
      (node (ref "C4") (pin "2") (pinfunction "2_2") (pintype "passive"))
      (node (ref "C40") (pin "2") (pinfunction "2_2") (pintype "passive"))
      (node (ref "C41") (pin "-") (pinfunction "-_-") (pintype "passive"))
      (node (ref "C42") (pin "2") (pinfunction "2_2") (pintype "passive"))
      (node (ref "C43") (pin "2") (pinfunction "2_2") (pintype "passive"))
      (node (ref "C44") (pin "2") (pinfunction "2_2") (pintype "passive"))
      (node (ref "C45") (pin "2") (pinfunction "2_2") (pintype "passive"))
      (node (ref "C46") (pin "2") (pinfunction "2_2") (pintype "passive"))
      (node (ref "C5") (pin "2") (pinfunction "2_2") (pintype "passive"))
      (node (ref "C6") (pin "2") (pinfunction "2_2") (pintype "passive"))
      (node (ref "C7") (pin "2") (pinfunction "2_2") (pintype "passive"))
      (node (ref "C8") (pin "2") (pinfunction "2_2") (pintype "passive"))
      (node (ref "C9") (pin "2") (pinfunction "2_2") (pintype "passive"))
      (node (ref "CLKIN") (pin "5") (pinfunction "5_5") (pintype "passive"))
      (node (ref "CUSB") (pin "2") (pinfunction "2_2") (pintype "passive"))
      (node (ref "IC1") (pin "P$2") (pinfunction "GND_P$2") (pintype "bidirectional"))
      (node (ref "IC10") (pin "1") (pinfunction "P$1_1") (pintype "bidirectional"))
      (node (ref "IC10") (pin "3") (pinfunction "P$3_3") (pintype "bidirectional"))
      (node (ref "IC11") (pin "1") (pinfunction "P$1_1") (pintype "bidirectional"))
      (node (ref "IC11") (pin "3") (pinfunction "P$3_3") (pintype "bidirectional"))
      (node (ref "IC12") (pin "1") (pinfunction "P$1_1") (pintype "bidirectional"))
      (node (ref "IC12") (pin "3") (pinfunction "P$3_3") (pintype "bidirectional"))
      (node (ref "IC13") (pin "18") (pinfunction "GND_18") (pintype "power_in"))
      (node (ref "IC13") (pin "30") (pinfunction "GND_30") (pintype "power_in"))
      (node (ref "IC13") (pin "38") (pinfunction "GND_38") (pintype "power_in"))
      (node (ref "IC13") (pin "8") (pinfunction "GND_8") (pintype "power_in"))
      (node (ref "IC14") (pin "1") (pinfunction "P$1_1") (pintype "bidirectional"))
      (node (ref "IC14") (pin "3") (pinfunction "P$3_3") (pintype "bidirectional"))
      (node (ref "IC15") (pin "18") (pinfunction "GND_18") (pintype "power_in"))
      (node (ref "IC15") (pin "30") (pinfunction "GND_30") (pintype "power_in"))
      (node (ref "IC15") (pin "38") (pinfunction "GND_38") (pintype "power_in"))
      (node (ref "IC15") (pin "8") (pinfunction "GND_8") (pintype "power_in"))
      (node (ref "IC2") (pin "P3") (pinfunction "GND_P3") (pintype "passive"))
      (node (ref "IC3") (pin "2") (pinfunction "GND_2") (pintype "bidirectional"))
      (node (ref "IC4") (pin "18") (pinfunction "GND_18") (pintype "power_in"))
      (node (ref "IC4") (pin "21") (pinfunction "GND_21") (pintype "power_in"))
      (node (ref "IC4") (pin "25") (pinfunction "GND_25") (pintype "power_in"))
      (node (ref "IC4") (pin "26") (pinfunction "TEST_26") (pintype "input"))
      (node (ref "IC4") (pin "7") (pinfunction "GND_7") (pintype "power_in"))
      (node (ref "IC5") (pin "18") (pinfunction "GND_18") (pintype "power_in"))
      (node (ref "IC5") (pin "30") (pinfunction "GND_30") (pintype "power_in"))
      (node (ref "IC5") (pin "38") (pinfunction "GND_38") (pintype "power_in"))
      (node (ref "IC5") (pin "8") (pinfunction "GND_8") (pintype "power_in"))
      (node (ref "IC6") (pin "1") (pinfunction "P$1_1") (pintype "bidirectional"))
      (node (ref "IC6") (pin "3") (pinfunction "P$3_3") (pintype "bidirectional"))
      (node (ref "IC7") (pin "1") (pinfunction "P$1_1") (pintype "bidirectional"))
      (node (ref "IC7") (pin "3") (pinfunction "P$3_3") (pintype "bidirectional"))
      (node (ref "IC8") (pin "1") (pinfunction "P$1_1") (pintype "bidirectional"))
      (node (ref "IC8") (pin "3") (pinfunction "P$3_3") (pintype "bidirectional"))
      (node (ref "IC9") (pin "1") (pinfunction "P$1_1") (pintype "bidirectional"))
      (node (ref "IC9") (pin "3") (pinfunction "P$3_3") (pintype "bidirectional"))
      (node (ref "IN1") (pin "2") (pinfunction "2_2") (pintype "passive"))
      (node (ref "J1") (pin "3") (pinfunction "S_3") (pintype "passive"))
      (node (ref "J2") (pin "3") (pinfunction "S_3") (pintype "passive"))
      (node (ref "JACK") (pin "P2") (pinfunction "2_P2") (pintype "passive"))
      (node (ref "JACK") (pin "P3") (pinfunction "3_P3") (pintype "passive"))
      (node (ref "OSC") (pin "P$2") (pinfunction "GND_P$2") (pintype "passive"))
      (node (ref "OSC1") (pin "P$2") (pinfunction "GND_P$2") (pintype "passive"))
      (node (ref "OSC2") (pin "P$2") (pinfunction "GND_P$2") (pintype "passive"))
      (node (ref "OUT1") (pin "2") (pinfunction "2_2") (pintype "passive"))
      (node (ref "PDI") (pin "6") (pinfunction "6_6") (pintype "passive"))
      (node (ref "PDI1") (pin "6") (pinfunction "6_6") (pintype "passive"))
      (node (ref "PDI2") (pin "6") (pinfunction "6_6") (pintype "passive"))
      (node (ref "R5") (pin "1") (pinfunction "1_1") (pintype "passive"))
      (node (ref "RTRIM") (pin "1") (pinfunction "1_1") (pintype "passive"))
      (node (ref "RUSB") (pin "2") (pinfunction "2_2") (pintype "passive"))
      (node (ref "STATE") (pin "K") (pinfunction "K_K") (pintype "bidirectional"))
      (node (ref "USB") (pin "P$5") (pinfunction "5_P$5") (pintype "bidirectional"))
      (node (ref "X1") (pin "P2") (pinfunction "2_P2") (pintype "passive"))
      (node (ref "X1") (pin "P8") (pinfunction "8_P8") (pintype "passive"))
      (node (ref "X2") (pin "P2") (pinfunction "2_P2") (pintype "passive"))
      (node (ref "X3") (pin "P3") (pinfunction "3_P3") (pintype "passive"))
      (node (ref "X4") (pin "P3") (pinfunction "3_P3") (pintype "passive"))
    )
    (net (code "35") (name "IN0") (class "Default")
      (node (ref "IC5") (pin "40") (pinfunction "PA0/ADC0/AREF_40") (pintype "bidirectional"))
      (node (ref "R7") (pin "2") (pinfunction "2_2") (pintype "passive"))
    )
    (net (code "36") (name "LED_DATA0") (class "Default")
      (node (ref "IC12") (pin "2") (pinfunction "P$2_2") (pintype "bidirectional"))
      (node (ref "IC13") (pin "15") (pinfunction "PC5/OC1B/MOSI/XCK1_15") (pintype "bidirectional"))
    )
    (net (code "37") (name "LED_DATA1") (class "Default")
      (node (ref "IC14") (pin "2") (pinfunction "P$2_2") (pintype "bidirectional"))
      (node (ref "IC15") (pin "15") (pinfunction "PC5/OC1B/MOSI/XCK1_15") (pintype "bidirectional"))
    )
    (net (code "38") (name "Net-(CTUNE-Pad1)") (class "Default")
      (node (ref "CTUNE") (pin "1") (pinfunction "1_1") (pintype "passive"))
      (node (ref "RTUNE") (pin "1") (pinfunction "1_1") (pintype "passive"))
    )
    (net (code "39") (name "Net-(IC1-VBUS)") (class "Default")
      (node (ref "C4") (pin "1") (pinfunction "1_1") (pintype "passive"))
      (node (ref "IC1") (pin "P$5") (pinfunction "VBUS_P$5") (pintype "bidirectional"))
      (node (ref "L1") (pin "2") (pinfunction "2_2") (pintype "passive"))
      (node (ref "USB") (pin "P$1") (pinfunction "1_P$1") (pintype "bidirectional"))
    )
    (net (code "40") (name "Net-(IC2-ON{slash}OFF)") (class "Default")
      (node (ref "IC2") (pin "P1") (pinfunction "ON/OFF_P1") (pintype "passive"))
      (node (ref "R1") (pin "1") (pinfunction "1_1") (pintype "passive"))
    )
    (net (code "41") (name "Net-(IC2-TRIM)") (class "Default")
      (node (ref "CTUNE") (pin "2") (pinfunction "2_2") (pintype "passive"))
      (node (ref "IC2") (pin "P5") (pinfunction "TRIM_P5") (pintype "passive"))
      (node (ref "RTRIM") (pin "2") (pinfunction "2_2") (pintype "passive"))
    )
    (net (code "42") (name "Net-(IC4-3V3OUT)") (class "Default")
      (node (ref "C13") (pin "1") (pinfunction "1_1") (pintype "passive"))
      (node (ref "IC4") (pin "17") (pinfunction "3V3OUT_17") (pintype "output"))
    )
    (net (code "43") (name "Net-(IC4-CBUS0)") (class "Default")
      (node (ref "IC4") (pin "23") (pinfunction "CBUS0_23") (pintype "bidirectional"))
      (node (ref "TX") (pin "K") (pinfunction "K_K") (pintype "bidirectional"))
    )
    (net (code "44") (name "Net-(IC4-CBUS1)") (class "Default")
      (node (ref "IC4") (pin "22") (pinfunction "CBUS1_22") (pintype "bidirectional"))
      (node (ref "RX") (pin "K") (pinfunction "K_K") (pintype "bidirectional"))
    )
    (net (code "45") (name "Net-(IC5-PR1{slash}XTAL1)") (class "Default")
      (node (ref "IC5") (pin "37") (pinfunction "PR1/XTAL1_37") (pintype "bidirectional"))
      (node (ref "OSC") (pin "P$3") (pinfunction "OUTPUT_P$3") (pintype "passive"))
    )
    (net (code "46") (name "Net-(IC6-P$4)") (class "Default")
      (node (ref "IC6") (pin "4") (pinfunction "P$4_4") (pintype "bidirectional"))
      (node (ref "R7") (pin "1") (pinfunction "1_1") (pintype "passive"))
    )
    (net (code "47") (name "Net-(IC7-P$4)") (class "Default")
      (node (ref "IC7") (pin "4") (pinfunction "P$4_4") (pintype "bidirectional"))
      (node (ref "R8") (pin "1") (pinfunction "1_1") (pintype "passive"))
    )
    (net (code "48") (name "Net-(IC8-P$4)") (class "Default")
      (node (ref "IC8") (pin "4") (pinfunction "P$4_4") (pintype "bidirectional"))
      (node (ref "R9") (pin "1") (pinfunction "1_1") (pintype "passive"))
    )
    (net (code "49") (name "Net-(IC9-P$4)") (class "Default")
      (node (ref "IC9") (pin "4") (pinfunction "P$4_4") (pintype "bidirectional"))
      (node (ref "R10") (pin "1") (pinfunction "1_1") (pintype "passive"))
    )
    (net (code "50") (name "Net-(IC10-P$4)") (class "Default")
      (node (ref "IC10") (pin "4") (pinfunction "P$4_4") (pintype "bidirectional"))
      (node (ref "R11") (pin "1") (pinfunction "1_1") (pintype "passive"))
    )
    (net (code "51") (name "Net-(IC11-P$4)") (class "Default")
      (node (ref "IC11") (pin "4") (pinfunction "P$4_4") (pintype "bidirectional"))
      (node (ref "R12") (pin "1") (pinfunction "1_1") (pintype "passive"))
    )
    (net (code "52") (name "Net-(IC12-P$4)") (class "Default")
      (node (ref "IC12") (pin "4") (pinfunction "P$4_4") (pintype "bidirectional"))
      (node (ref "R13") (pin "2") (pinfunction "2_2") (pintype "passive"))
    )
    (net (code "53") (name "Net-(IC13-PR1{slash}XTAL1)") (class "Default")
      (node (ref "IC13") (pin "37") (pinfunction "PR1/XTAL1_37") (pintype "bidirectional"))
      (node (ref "OSC1") (pin "P$3") (pinfunction "OUTPUT_P$3") (pintype "passive"))
    )
    (net (code "54") (name "Net-(IC14-P$4)") (class "Default")
      (node (ref "IC14") (pin "4") (pinfunction "P$4_4") (pintype "bidirectional"))
      (node (ref "R14") (pin "2") (pinfunction "2_2") (pintype "passive"))
    )
    (net (code "55") (name "Net-(IC15-PR1{slash}XTAL1)") (class "Default")
      (node (ref "IC15") (pin "37") (pinfunction "PR1/XTAL1_37") (pintype "bidirectional"))
      (node (ref "OSC2") (pin "P$3") (pinfunction "OUTPUT_P$3") (pintype "passive"))
    )
    (net (code "56") (name "Net-(R2-Pad1)") (class "Default")
      (node (ref "R2") (pin "1") (pinfunction "1_1") (pintype "passive"))
      (node (ref "TX") (pin "A") (pinfunction "A_A") (pintype "bidirectional"))
    )
    (net (code "57") (name "Net-(R3-Pad1)") (class "Default")
      (node (ref "R3") (pin "1") (pinfunction "1_1") (pintype "passive"))
      (node (ref "RX") (pin "A") (pinfunction "A_A") (pintype "bidirectional"))
    )
    (net (code "58") (name "Net-(R6-Pad1)") (class "Default")
      (node (ref "R6") (pin "1") (pinfunction "1_1") (pintype "passive"))
      (node (ref "STATE") (pin "A") (pinfunction "A_A") (pintype "bidirectional"))
    )
    (net (code "59") (name "Net-(USB-2)") (class "Default")
      (node (ref "IC1") (pin "P$1") (pinfunction "IO1_P$1") (pintype "bidirectional"))
      (node (ref "USB") (pin "P$2") (pinfunction "2_P$2") (pintype "bidirectional"))
    )
    (net (code "60") (name "Net-(USB-3)") (class "Default")
      (node (ref "IC1") (pin "P$3") (pinfunction "IO2_P$3") (pintype "bidirectional"))
      (node (ref "USB") (pin "P$3") (pinfunction "3_P$3") (pintype "bidirectional"))
    )
    (net (code "61") (name "Net-(USB-P$1)") (class "Default")
      (node (ref "RUSB") (pin "1") (pinfunction "1_1") (pintype "passive"))
      (node (ref "USB") (pin "SHIELD_1") (pinfunction "P$1_SHIELD_1") (pintype "bidirectional"))
    )
    (net (code "62") (name "Net-(USB-P$4)") (class "Default")
      (node (ref "CUSB") (pin "1") (pinfunction "1_1") (pintype "passive"))
      (node (ref "USB") (pin "SHIELD_4") (pinfunction "P$4_SHIELD_4") (pintype "bidirectional"))
    )
    (net (code "63") (name "OUT0") (class "Default")
      (node (ref "IC5") (pin "41") (pinfunction "PA1/ADC1_41") (pintype "bidirectional"))
      (node (ref "IC7") (pin "2") (pinfunction "P$2_2") (pintype "bidirectional"))
    )
    (net (code "64") (name "OUT1") (class "Default")
      (node (ref "IC5") (pin "42") (pinfunction "PA2/ADC2_42") (pintype "bidirectional"))
      (node (ref "IC8") (pin "2") (pinfunction "P$2_2") (pintype "bidirectional"))
    )
    (net (code "65") (name "OUT2") (class "Default")
      (node (ref "IC5") (pin "43") (pinfunction "PA3/ADC3_43") (pintype "bidirectional"))
      (node (ref "IC9") (pin "2") (pinfunction "P$2_2") (pintype "bidirectional"))
    )
    (net (code "66") (name "OUT3") (class "Default")
      (node (ref "IC10") (pin "2") (pinfunction "P$2_2") (pintype "bidirectional"))
      (node (ref "IC5") (pin "44") (pinfunction "PA4/ADC4_44") (pintype "bidirectional"))
    )
    (net (code "67") (name "OUT4") (class "Default")
      (node (ref "IC11") (pin "2") (pinfunction "P$2_2") (pintype "bidirectional"))
      (node (ref "IC5") (pin "1") (pinfunction "PA5/ADC5_1") (pintype "bidirectional"))
    )
    (net (code "68") (name "PDI-CLK") (class "Default")
      (node (ref "IC5") (pin "35") (pinfunction "RESET/PDI-CLK_35") (pintype "input"))
      (node (ref "PDI") (pin "5") (pinfunction "5_5") (pintype "passive"))
    )
    (net (code "69") (name "PDI-CLK0") (class "Default")
      (node (ref "IC13") (pin "35") (pinfunction "RESET/PDI-CLK_35") (pintype "input"))
      (node (ref "PDI1") (pin "5") (pinfunction "5_5") (pintype "passive"))
    )
    (net (code "70") (name "PDI-CLK1") (class "Default")
      (node (ref "IC15") (pin "35") (pinfunction "RESET/PDI-CLK_35") (pintype "input"))
      (node (ref "PDI2") (pin "5") (pinfunction "5_5") (pintype "passive"))
    )
    (net (code "71") (name "PDI-DATA") (class "Default")
      (node (ref "IC5") (pin "34") (pinfunction "PDI-DATA_34") (pintype "bidirectional"))
      (node (ref "PDI") (pin "1") (pinfunction "1_1") (pintype "passive"))
    )
    (net (code "72") (name "PDI-DATA0") (class "Default")
      (node (ref "IC13") (pin "34") (pinfunction "PDI-DATA_34") (pintype "bidirectional"))
      (node (ref "PDI1") (pin "1") (pinfunction "1_1") (pintype "passive"))
    )
    (net (code "73") (name "PDI-DATA1") (class "Default")
      (node (ref "IC15") (pin "34") (pinfunction "PDI-DATA_34") (pintype "bidirectional"))
      (node (ref "PDI2") (pin "1") (pinfunction "1_1") (pintype "passive"))
    )
    (net (code "74") (name "SERIAL_LED0") (class "Default")
      (node (ref "J1") (pin "2") (pinfunction "S_2") (pintype "passive"))
      (node (ref "R13") (pin "1") (pinfunction "1_1") (pintype "passive"))
      (node (ref "X3") (pin "P2") (pinfunction "2_P2") (pintype "passive"))
    )
    (net (code "75") (name "SERIAL_LED1") (class "Default")
      (node (ref "J2") (pin "2") (pinfunction "S_2") (pintype "passive"))
      (node (ref "R14") (pin "1") (pinfunction "1_1") (pintype "passive"))
      (node (ref "X4") (pin "P2") (pinfunction "2_P2") (pintype "passive"))
    )
    (net (code "76") (name "STATE") (class "Default")
      (node (ref "IC5") (pin "36") (pinfunction "PR0/XTAL2_36") (pintype "bidirectional"))
      (node (ref "R6") (pin "2") (pinfunction "2_2") (pintype "passive"))
    )
    (net (code "77") (name "UPDATE_LEDS0") (class "Default")
      (node (ref "IC13") (pin "12") (pinfunction "PC2/OC0C/RXD0_12") (pintype "bidirectional"))
      (node (ref "IC5") (pin "2") (pinfunction "PA6/ADC6_2") (pintype "bidirectional"))
    )
    (net (code "78") (name "UPDATE_LEDS1") (class "Default")
      (node (ref "IC15") (pin "12") (pinfunction "PC2/OC0C/RXD0_12") (pintype "bidirectional"))
      (node (ref "IC5") (pin "13") (pinfunction "PC3/OC0D/TXD0_13") (pintype "bidirectional"))
    )
    (net (code "79") (name "USBDM") (class "Default")
      (node (ref "C7") (pin "1") (pinfunction "1_1") (pintype "passive"))
      (node (ref "IC1") (pin "P$6") (pinfunction "IO1_P$6") (pintype "bidirectional"))
      (node (ref "IC4") (pin "16") (pinfunction "USBDM_16") (pintype "bidirectional"))
    )
    (net (code "80") (name "USBDP") (class "Default")
      (node (ref "C6") (pin "1") (pinfunction "1_1") (pintype "passive"))
      (node (ref "IC1") (pin "P$4") (pinfunction "IO2_P$4") (pintype "bidirectional"))
      (node (ref "IC4") (pin "15") (pinfunction "USBDP_15") (pintype "bidirectional"))
    )
    (net (code "81") (name "VCCIO") (class "Default")
      (node (ref "C15") (pin "1") (pinfunction "1_1") (pintype "passive"))
      (node (ref "C17") (pin "1") (pinfunction "1_1") (pintype "passive"))
      (node (ref "C18") (pin "1") (pinfunction "1_1") (pintype "passive"))
      (node (ref "C19") (pin "1") (pinfunction "1_1") (pintype "passive"))
      (node (ref "C20") (pin "1") (pinfunction "1_1") (pintype "passive"))
      (node (ref "C21") (pin "1") (pinfunction "1_1") (pintype "passive"))
      (node (ref "C22") (pin "1") (pinfunction "1_1") (pintype "passive"))
      (node (ref "C23") (pin "1") (pinfunction "1_1") (pintype "passive"))
      (node (ref "C31") (pin "1") (pinfunction "1_1") (pintype "passive"))
      (node (ref "C34") (pin "1") (pinfunction "1_1") (pintype "passive"))
      (node (ref "C35") (pin "1") (pinfunction "1_1") (pintype "passive"))
      (node (ref "C36") (pin "1") (pinfunction "1_1") (pintype "passive"))
      (node (ref "C37") (pin "1") (pinfunction "1_1") (pintype "passive"))
      (node (ref "C38") (pin "1") (pinfunction "1_1") (pintype "passive"))
      (node (ref "C39") (pin "1") (pinfunction "1_1") (pintype "passive"))
      (node (ref "C42") (pin "1") (pinfunction "1_1") (pintype "passive"))
      (node (ref "C43") (pin "1") (pinfunction "1_1") (pintype "passive"))
      (node (ref "C44") (pin "1") (pinfunction "1_1") (pintype "passive"))
      (node (ref "C45") (pin "1") (pinfunction "1_1") (pintype "passive"))
      (node (ref "C46") (pin "1") (pinfunction "1_1") (pintype "passive"))
      (node (ref "CLKIN") (pin "1") (pinfunction "1_1") (pintype "passive"))
      (node (ref "IC13") (pin "19") (pinfunction "VCC_19") (pintype "power_in"))
      (node (ref "IC13") (pin "31") (pinfunction "VCC_31") (pintype "power_in"))
      (node (ref "IC13") (pin "39") (pinfunction "AVCC_39") (pintype "power_in"))
      (node (ref "IC13") (pin "9") (pinfunction "VCC_9") (pintype "power_in"))
      (node (ref "IC15") (pin "19") (pinfunction "VCC_19") (pintype "power_in"))
      (node (ref "IC15") (pin "31") (pinfunction "VCC_31") (pintype "power_in"))
      (node (ref "IC15") (pin "39") (pinfunction "AVCC_39") (pintype "power_in"))
      (node (ref "IC15") (pin "9") (pinfunction "VCC_9") (pintype "power_in"))
      (node (ref "IC3") (pin "5") (pinfunction "OUT_5") (pintype "bidirectional"))
      (node (ref "IC4") (pin "4") (pinfunction "VCCIO_4") (pintype "power_in"))
      (node (ref "IC5") (pin "19") (pinfunction "VCC_19") (pintype "power_in"))
      (node (ref "IC5") (pin "31") (pinfunction "VCC_31") (pintype "power_in"))
      (node (ref "IC5") (pin "39") (pinfunction "AVCC_39") (pintype "power_in"))
      (node (ref "IC5") (pin "9") (pinfunction "VCC_9") (pintype "power_in"))
      (node (ref "IC6") (pin "5") (pinfunction "P$5_5") (pintype "bidirectional"))
      (node (ref "JP1") (pin "1") (pinfunction "1_1") (pintype "passive"))
      (node (ref "OSC") (pin "P$4") (pinfunction "VDD_P$4") (pintype "passive"))
      (node (ref "OSC1") (pin "P$4") (pinfunction "VDD_P$4") (pintype "passive"))
      (node (ref "OSC2") (pin "P$4") (pinfunction "VDD_P$4") (pintype "passive"))
      (node (ref "PDI") (pin "2") (pinfunction "2_2") (pintype "passive"))
      (node (ref "PDI1") (pin "2") (pinfunction "2_2") (pintype "passive"))
      (node (ref "PDI2") (pin "2") (pinfunction "2_2") (pintype "passive"))
    )
    (net (code "82") (name "unconnected-(IC3-N{slash}C-Pad4)") (class "Default")
      (node (ref "IC3") (pin "4") (pinfunction "N/C_4") (pintype "bidirectional"))
    )
    (net (code "83") (name "unconnected-(IC4-CBUS2-Pad13)") (class "Default")
      (node (ref "IC4") (pin "13") (pinfunction "CBUS2_13") (pintype "bidirectional"))
    )
    (net (code "84") (name "unconnected-(IC4-CBUS3-Pad14)") (class "Default")
      (node (ref "IC4") (pin "14") (pinfunction "CBUS3_14") (pintype "bidirectional"))
    )
    (net (code "85") (name "unconnected-(IC4-CBUS4-Pad12)") (class "Default")
      (node (ref "IC4") (pin "12") (pinfunction "CBUS4_12") (pintype "bidirectional"))
    )
    (net (code "86") (name "unconnected-(IC4-OSCI-Pad27)") (class "Default")
      (node (ref "IC4") (pin "27") (pinfunction "OSCI_27") (pintype "input"))
    )
    (net (code "87") (name "unconnected-(IC4-OSCO-Pad28)") (class "Default")
      (node (ref "IC4") (pin "28") (pinfunction "OSCO_28") (pintype "output"))
    )
    (net (code "88") (name "unconnected-(IC4-~{DCD}-Pad10)") (class "Default")
      (node (ref "IC4") (pin "10") (pinfunction "~{DCD}_10") (pintype "input"))
    )
    (net (code "89") (name "unconnected-(IC4-~{DSR}-Pad9)") (class "Default")
      (node (ref "IC4") (pin "9") (pinfunction "~{DSR}_9") (pintype "input"))
    )
    (net (code "90") (name "unconnected-(IC4-~{DTR}-Pad2)") (class "Default")
      (node (ref "IC4") (pin "2") (pinfunction "~{DTR}_2") (pintype "output"))
    )
    (net (code "91") (name "unconnected-(IC4-~{RESET}-Pad19)") (class "Default")
      (node (ref "IC4") (pin "19") (pinfunction "~{RESET}_19") (pintype "input"))
    )
    (net (code "92") (name "unconnected-(IC4-~{RI}-Pad6)") (class "Default")
      (node (ref "IC4") (pin "6") (pinfunction "~{RI}_6") (pintype "input"))
    )
    (net (code "93") (name "unconnected-(IC5-PB3{slash}ADC11{slash}DAC1-Pad7)") (class "Default")
      (node (ref "IC5") (pin "7") (pinfunction "PB3/ADC11/DAC1_7") (pintype "bidirectional"))
    )
    (net (code "94") (name "unconnected-(IC5-PC0{slash}OC0A{slash}SDA-Pad10)") (class "Default")
      (node (ref "IC5") (pin "10") (pinfunction "PC0/OC0A/SDA_10") (pintype "bidirectional"))
    )
    (net (code "95") (name "unconnected-(IC5-PC1{slash}OC0B{slash}XCK0{slash}SCL-Pad11)") (class "Default")
      (node (ref "IC5") (pin "11") (pinfunction "PC1/OC0B/XCK0/SCL_11") (pintype "bidirectional"))
    )
    (net (code "96") (name "unconnected-(IC13-PA0{slash}ADC0{slash}AREF-Pad40)") (class "Default")
      (node (ref "IC13") (pin "40") (pinfunction "PA0/ADC0/AREF_40") (pintype "bidirectional"))
    )
    (net (code "97") (name "unconnected-(IC13-PA1{slash}ADC1-Pad41)") (class "Default")
      (node (ref "IC13") (pin "41") (pinfunction "PA1/ADC1_41") (pintype "bidirectional"))
    )
    (net (code "98") (name "unconnected-(IC13-PA2{slash}ADC2-Pad42)") (class "Default")
      (node (ref "IC13") (pin "42") (pinfunction "PA2/ADC2_42") (pintype "bidirectional"))
    )
    (net (code "99") (name "unconnected-(IC13-PA3{slash}ADC3-Pad43)") (class "Default")
      (node (ref "IC13") (pin "43") (pinfunction "PA3/ADC3_43") (pintype "bidirectional"))
    )
    (net (code "100") (name "unconnected-(IC13-PA4{slash}ADC4-Pad44)") (class "Default")
      (node (ref "IC13") (pin "44") (pinfunction "PA4/ADC4_44") (pintype "bidirectional"))
    )
    (net (code "101") (name "unconnected-(IC13-PA5{slash}ADC5-Pad1)") (class "Default")
      (node (ref "IC13") (pin "1") (pinfunction "PA5/ADC5_1") (pintype "bidirectional"))
    )
    (net (code "102") (name "unconnected-(IC13-PA6{slash}ADC6-Pad2)") (class "Default")
      (node (ref "IC13") (pin "2") (pinfunction "PA6/ADC6_2") (pintype "bidirectional"))
    )
    (net (code "103") (name "unconnected-(IC13-PA7{slash}ADC7{slash}AC0-OUT-Pad3)") (class "Default")
      (node (ref "IC13") (pin "3") (pinfunction "PA7/ADC7/AC0-OUT_3") (pintype "bidirectional"))
    )
    (net (code "104") (name "unconnected-(IC13-PB0{slash}ADC8{slash}AREF-Pad4)") (class "Default")
      (node (ref "IC13") (pin "4") (pinfunction "PB0/ADC8/AREF_4") (pintype "bidirectional"))
    )
    (net (code "105") (name "unconnected-(IC13-PB1{slash}ADC9-Pad5)") (class "Default")
      (node (ref "IC13") (pin "5") (pinfunction "PB1/ADC9_5") (pintype "bidirectional"))
    )
    (net (code "106") (name "unconnected-(IC13-PB2{slash}ADC10{slash}DAC0-Pad6)") (class "Default")
      (node (ref "IC13") (pin "6") (pinfunction "PB2/ADC10/DAC0_6") (pintype "bidirectional"))
    )
    (net (code "107") (name "unconnected-(IC13-PB3{slash}ADC11{slash}DAC1-Pad7)") (class "Default")
      (node (ref "IC13") (pin "7") (pinfunction "PB3/ADC11/DAC1_7") (pintype "bidirectional"))
    )
    (net (code "108") (name "unconnected-(IC13-PC0{slash}OC0A{slash}SDA-Pad10)") (class "Default")
      (node (ref "IC13") (pin "10") (pinfunction "PC0/OC0A/SDA_10") (pintype "bidirectional"))
    )
    (net (code "109") (name "unconnected-(IC13-PC1{slash}OC0B{slash}XCK0{slash}SCL-Pad11)") (class "Default")
      (node (ref "IC13") (pin "11") (pinfunction "PC1/OC0B/XCK0/SCL_11") (pintype "bidirectional"))
    )
    (net (code "110") (name "unconnected-(IC13-PC6{slash}MISO{slash}RXD1-Pad16)") (class "Default")
      (node (ref "IC13") (pin "16") (pinfunction "PC6/MISO/RXD1_16") (pintype "bidirectional"))
    )
    (net (code "111") (name "unconnected-(IC13-PC7{slash}SCK{slash}TXD1{slash}CLKO{slash}EVO-Pad17)") (class "Default")
      (node (ref "IC13") (pin "17") (pinfunction "PC7/SCK/TXD1/CLKO/EVO_17") (pintype "bidirectional"))
    )
    (net (code "112") (name "unconnected-(IC13-PR0{slash}XTAL2-Pad36)") (class "Default")
      (node (ref "IC13") (pin "36") (pinfunction "PR0/XTAL2_36") (pintype "bidirectional"))
    )
    (net (code "113") (name "unconnected-(IC13-~RXD0OC0CPE2-Pad32)") (class "Default")
      (node (ref "IC13") (pin "32") (pinfunction "~RXD0OC0CPE2_32") (pintype "bidirectional"))
    )
    (net (code "114") (name "unconnected-(IC13-~RXD1MISOPD6-Pad26)") (class "Default")
      (node (ref "IC13") (pin "26") (pinfunction "~RXD1MISOPD6_26") (pintype "bidirectional"))
    )
    (net (code "115") (name "unconnected-(IC13-~TXD0OC0DPE3-Pad33)") (class "Default")
      (node (ref "IC13") (pin "33") (pinfunction "~TXD0OC0DPE3_33") (pintype "bidirectional"))
    )
    (net (code "116") (name "unconnected-(IC13-~XCK1MOSIPD5-Pad25)") (class "Default")
      (node (ref "IC13") (pin "25") (pinfunction "~XCK1MOSIPD5_25") (pintype "bidirectional"))
    )
    (net (code "117") (name "unconnected-(IC13-~{#SSPD4}-Pad24)") (class "Default")
      (node (ref "IC13") (pin "24") (pinfunction "~{#SSPD4}_24") (pintype "bidirectional"))
    )
    (net (code "118") (name "unconnected-(IC13-~~{TXD1SCKCLKOPD7}-Pad27)") (class "Default")
      (node (ref "IC13") (pin "27") (pinfunction "~~{TXD1SCKCLKOPD7}_27") (pintype "bidirectional"))
    )
    (net (code "119") (name "unconnected-(IC15-PA0{slash}ADC0{slash}AREF-Pad40)") (class "Default")
      (node (ref "IC15") (pin "40") (pinfunction "PA0/ADC0/AREF_40") (pintype "bidirectional"))
    )
    (net (code "120") (name "unconnected-(IC15-PA1{slash}ADC1-Pad41)") (class "Default")
      (node (ref "IC15") (pin "41") (pinfunction "PA1/ADC1_41") (pintype "bidirectional"))
    )
    (net (code "121") (name "unconnected-(IC15-PA2{slash}ADC2-Pad42)") (class "Default")
      (node (ref "IC15") (pin "42") (pinfunction "PA2/ADC2_42") (pintype "bidirectional"))
    )
    (net (code "122") (name "unconnected-(IC15-PA3{slash}ADC3-Pad43)") (class "Default")
      (node (ref "IC15") (pin "43") (pinfunction "PA3/ADC3_43") (pintype "bidirectional"))
    )
    (net (code "123") (name "unconnected-(IC15-PA4{slash}ADC4-Pad44)") (class "Default")
      (node (ref "IC15") (pin "44") (pinfunction "PA4/ADC4_44") (pintype "bidirectional"))
    )
    (net (code "124") (name "unconnected-(IC15-PA5{slash}ADC5-Pad1)") (class "Default")
      (node (ref "IC15") (pin "1") (pinfunction "PA5/ADC5_1") (pintype "bidirectional"))
    )
    (net (code "125") (name "unconnected-(IC15-PA6{slash}ADC6-Pad2)") (class "Default")
      (node (ref "IC15") (pin "2") (pinfunction "PA6/ADC6_2") (pintype "bidirectional"))
    )
    (net (code "126") (name "unconnected-(IC15-PA7{slash}ADC7{slash}AC0-OUT-Pad3)") (class "Default")
      (node (ref "IC15") (pin "3") (pinfunction "PA7/ADC7/AC0-OUT_3") (pintype "bidirectional"))
    )
    (net (code "127") (name "unconnected-(IC15-PB0{slash}ADC8{slash}AREF-Pad4)") (class "Default")
      (node (ref "IC15") (pin "4") (pinfunction "PB0/ADC8/AREF_4") (pintype "bidirectional"))
    )
    (net (code "128") (name "unconnected-(IC15-PB1{slash}ADC9-Pad5)") (class "Default")
      (node (ref "IC15") (pin "5") (pinfunction "PB1/ADC9_5") (pintype "bidirectional"))
    )
    (net (code "129") (name "unconnected-(IC15-PB2{slash}ADC10{slash}DAC0-Pad6)") (class "Default")
      (node (ref "IC15") (pin "6") (pinfunction "PB2/ADC10/DAC0_6") (pintype "bidirectional"))
    )
    (net (code "130") (name "unconnected-(IC15-PB3{slash}ADC11{slash}DAC1-Pad7)") (class "Default")
      (node (ref "IC15") (pin "7") (pinfunction "PB3/ADC11/DAC1_7") (pintype "bidirectional"))
    )
    (net (code "131") (name "unconnected-(IC15-PC0{slash}OC0A{slash}SDA-Pad10)") (class "Default")
      (node (ref "IC15") (pin "10") (pinfunction "PC0/OC0A/SDA_10") (pintype "bidirectional"))
    )
    (net (code "132") (name "unconnected-(IC15-PC1{slash}OC0B{slash}XCK0{slash}SCL-Pad11)") (class "Default")
      (node (ref "IC15") (pin "11") (pinfunction "PC1/OC0B/XCK0/SCL_11") (pintype "bidirectional"))
    )
    (net (code "133") (name "unconnected-(IC15-PC6{slash}MISO{slash}RXD1-Pad16)") (class "Default")
      (node (ref "IC15") (pin "16") (pinfunction "PC6/MISO/RXD1_16") (pintype "bidirectional"))
    )
    (net (code "134") (name "unconnected-(IC15-PC7{slash}SCK{slash}TXD1{slash}CLKO{slash}EVO-Pad17)") (class "Default")
      (node (ref "IC15") (pin "17") (pinfunction "PC7/SCK/TXD1/CLKO/EVO_17") (pintype "bidirectional"))
    )
    (net (code "135") (name "unconnected-(IC15-PR0{slash}XTAL2-Pad36)") (class "Default")
      (node (ref "IC15") (pin "36") (pinfunction "PR0/XTAL2_36") (pintype "bidirectional"))
    )
    (net (code "136") (name "unconnected-(IC15-~RXD0OC0CPE2-Pad32)") (class "Default")
      (node (ref "IC15") (pin "32") (pinfunction "~RXD0OC0CPE2_32") (pintype "bidirectional"))
    )
    (net (code "137") (name "unconnected-(IC15-~RXD1MISOPD6-Pad26)") (class "Default")
      (node (ref "IC15") (pin "26") (pinfunction "~RXD1MISOPD6_26") (pintype "bidirectional"))
    )
    (net (code "138") (name "unconnected-(IC15-~TXD0OC0DPE3-Pad33)") (class "Default")
      (node (ref "IC15") (pin "33") (pinfunction "~TXD0OC0DPE3_33") (pintype "bidirectional"))
    )
    (net (code "139") (name "unconnected-(IC15-~XCK1MOSIPD5-Pad25)") (class "Default")
      (node (ref "IC15") (pin "25") (pinfunction "~XCK1MOSIPD5_25") (pintype "bidirectional"))
    )
    (net (code "140") (name "unconnected-(IC15-~{#SSPD4}-Pad24)") (class "Default")
      (node (ref "IC15") (pin "24") (pinfunction "~{#SSPD4}_24") (pintype "bidirectional"))
    )
    (net (code "141") (name "unconnected-(IC15-~~{TXD1SCKCLKOPD7}-Pad27)") (class "Default")
      (node (ref "IC15") (pin "27") (pinfunction "~~{TXD1SCKCLKOPD7}_27") (pintype "bidirectional"))
    )
    (net (code "142") (name "unconnected-(OSC-STANDBY#-PadP$1)") (class "Default")
      (node (ref "OSC") (pin "P$1") (pinfunction "STANDBY#_P$1") (pintype "passive"))
    )
    (net (code "143") (name "unconnected-(OSC1-STANDBY#-PadP$1)") (class "Default")
      (node (ref "OSC1") (pin "P$1") (pinfunction "STANDBY#_P$1") (pintype "passive"))
    )
    (net (code "144") (name "unconnected-(OSC2-STANDBY#-PadP$1)") (class "Default")
      (node (ref "OSC2") (pin "P$1") (pinfunction "STANDBY#_P$1") (pintype "passive"))
    )
    (net (code "145") (name "unconnected-(PDI-Pad3)") (class "Default")
      (node (ref "PDI") (pin "3") (pinfunction "3_3") (pintype "passive"))
    )
    (net (code "146") (name "unconnected-(PDI-Pad4)") (class "Default")
      (node (ref "PDI") (pin "4") (pinfunction "4_4") (pintype "passive"))
    )
    (net (code "147") (name "unconnected-(PDI1-Pad3)") (class "Default")
      (node (ref "PDI1") (pin "3") (pinfunction "3_3") (pintype "passive"))
    )
    (net (code "148") (name "unconnected-(PDI1-Pad4)") (class "Default")
      (node (ref "PDI1") (pin "4") (pinfunction "4_4") (pintype "passive"))
    )
    (net (code "149") (name "unconnected-(PDI2-Pad3)") (class "Default")
      (node (ref "PDI2") (pin "3") (pinfunction "3_3") (pintype "passive"))
    )
    (net (code "150") (name "unconnected-(PDI2-Pad4)") (class "Default")
      (node (ref "PDI2") (pin "4") (pinfunction "4_4") (pintype "passive"))
    )
    (net (code "151") (name "unconnected-(USB-4-PadP$4)") (class "Default")
      (node (ref "USB") (pin "P$4") (pinfunction "4_P$4") (pintype "bidirectional"))
    )
    (net (code "152") (name "unconnected-(USB-P$2-PadSHIELD_2)") (class "Default")
      (node (ref "USB") (pin "SHIELD_2") (pinfunction "P$2_SHIELD_2") (pintype "bidirectional"))
    )
    (net (code "153") (name "unconnected-(USB-P$3-PadSHIELD_3)") (class "Default")
      (node (ref "USB") (pin "SHIELD_3") (pinfunction "P$3_SHIELD_3") (pintype "bidirectional"))
    )
  )
)
